# Sheet1.net
KiCad netlist of a schematic drawn in Altium Designer
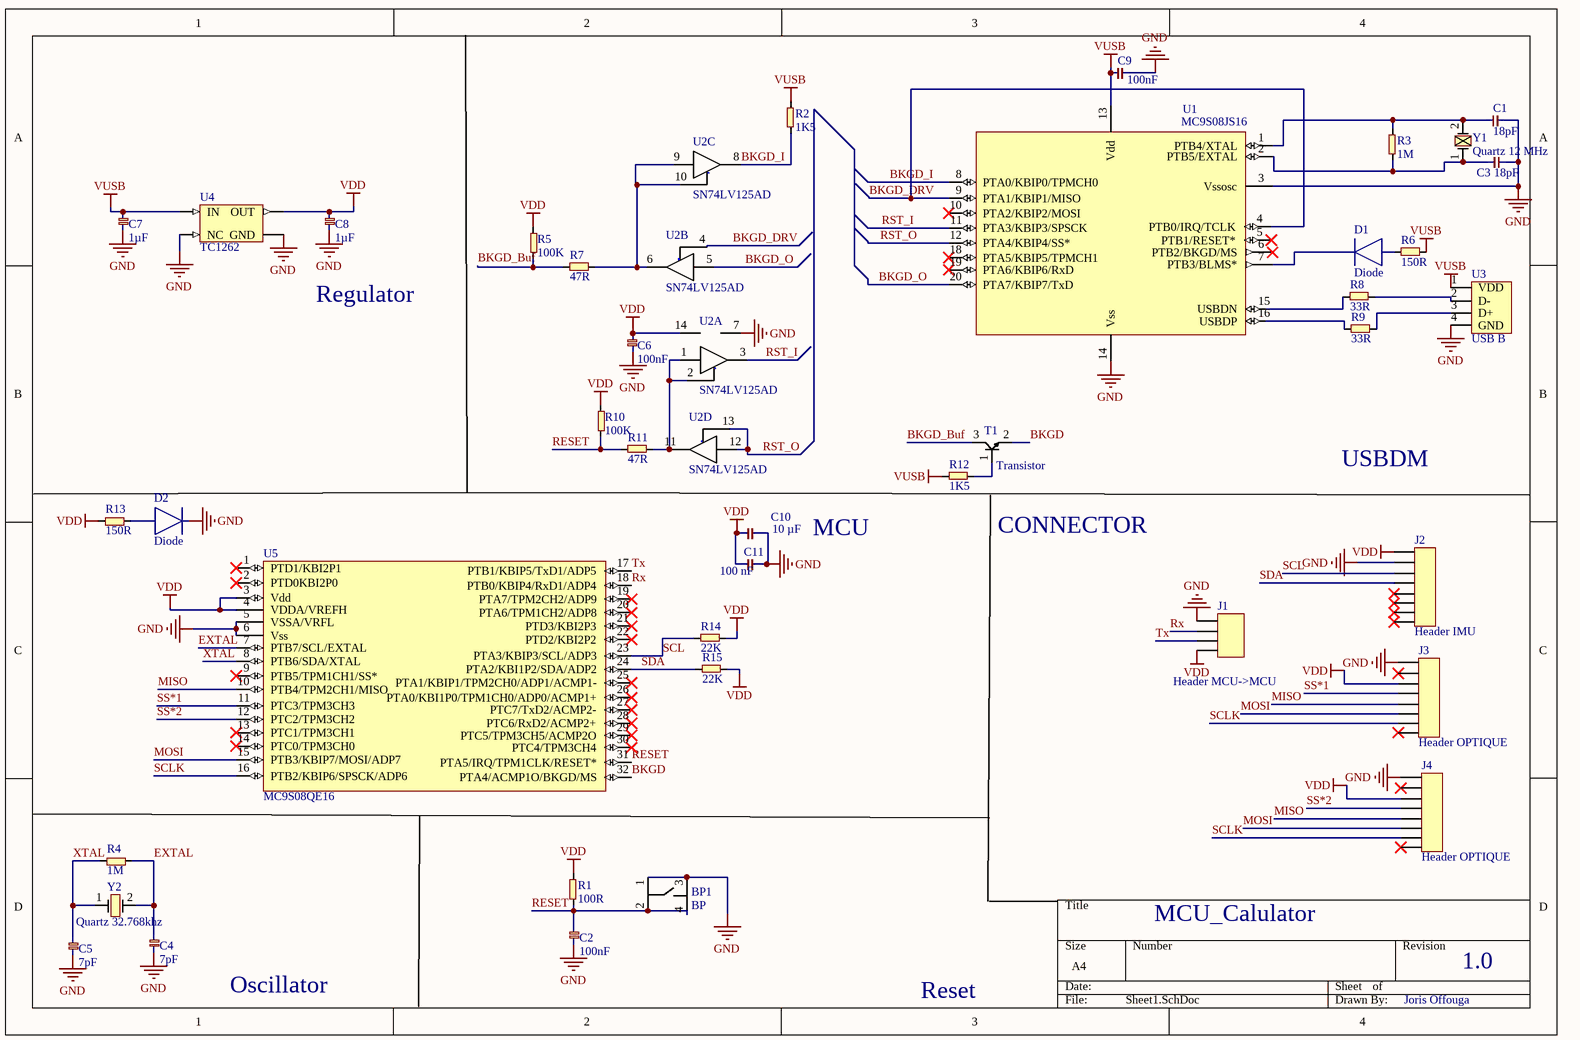
[diagram p0: Sheet1.SchDoc]

(export (version "E")
  (design (tool "Eeschema 10.0.6"))
  (components
    (comp (ref "BP1") (value "BP") (footprint "BP") (libsource (lib "Schlib1") (part "BP")))
    (comp (ref "C1")
      (value "18pF")
      (footprint "0805")
      (description "Condensateur")
      (libsource (lib "") (part "Condensateur_1"))
    )
    (comp (ref "C2")
      (value "100nF")
      (footprint "0805")
      (description "Condensateur")
      (libsource (lib "") (part "Condensateur_2"))
    )
    (comp (ref "C3")
      (value "18pF")
      (footprint "0805")
      (description "Condensateur")
      (libsource (lib "") (part "Condensateur_1"))
    )
    (comp (ref "C4")
      (value "7pF")
      (footprint "0805")
      (description "Condensateur")
      (libsource (lib "") (part "Condensateur_2"))
    )
    (comp (ref "C5")
      (value "7pF")
      (footprint "0805")
      (description "Condensateur")
      (libsource (lib "") (part "Condensateur_2"))
    )
    (comp (ref "C6")
      (value "100nF")
      (footprint "0805")
      (description "Condensateur")
      (libsource (lib "Schlib1") (part "Condensateur"))
    )
    (comp (ref "C7")
      (value "1µF")
      (footprint "0805")
      (description "Condensateur")
      (libsource (lib "") (part "Condensateur_2"))
    )
    (comp (ref "C8")
      (value "1µF")
      (footprint "0805")
      (description "Condensateur")
      (libsource (lib "") (part "Condensateur_2"))
    )
    (comp (ref "C9")
      (value "100nF")
      (footprint "0805")
      (description "Condensateur")
      (libsource (lib "") (part "Condensateur_1"))
    )
    (comp (ref "C10")
      (value "10 µF")
      (footprint "0805")
      (description "Condensateur")
      (libsource (lib "") (part "Condensateur_1"))
    )
    (comp (ref "C11")
      (value "100 nF")
      (footprint "0805")
      (description "Condensateur")
      (libsource (lib "") (part "Condensateur_1"))
    )
    (comp (ref "D1")
      (value "Diode")
      (footprint "led")
      (description "led")
      (libsource (lib "Schlib1") (part "Diode"))
    )
    (comp (ref "D2")
      (value "Diode")
      (footprint "led")
      (description "led")
      (libsource (lib "Schlib1") (part "Diode"))
    )
    (comp (ref "J1")
      (value "Header MCU->MCU")
      (footprint "Header 4")
      (libsource (lib "Schlib1") (part "Header 4"))
    )
    (comp (ref "J2") (value "Header IMU") (footprint "Header 8") (libsource (lib "Schlib1") (part "Header")))
    (comp (ref "J3")
      (value "Header OPTIQUE")
      (footprint "Header 8")
      (libsource (lib "Schlib1") (part "Header"))
    )
    (comp (ref "J4")
      (value "Header OPTIQUE")
      (footprint "Header 8")
      (libsource (lib "Schlib1") (part "Header"))
    )
    (comp (ref "R1") (value "100R") (footprint "0805") (libsource (lib "") (part "Resistance_2")))
    (comp (ref "R2") (value "1K5") (footprint "0805") (libsource (lib "") (part "Resistance_2")))
    (comp (ref "R3") (value "1M") (footprint "0805") (libsource (lib "") (part "Resistance_2")))
    (comp (ref "R4") (value "1M") (footprint "0805") (libsource (lib "") (part "Resistance_3")))
    (comp (ref "R5") (value "100K") (footprint "0805") (libsource (lib "Schlib1") (part "Resistance")))
    (comp (ref "R6") (value "150R") (footprint "0805") (libsource (lib "") (part "Resistance_1")))
    (comp (ref "R7") (value "47R") (footprint "0805") (libsource (lib "") (part "Resistance_1")))
    (comp (ref "R8") (value "33R") (footprint "0805") (libsource (lib "") (part "Resistance_1")))
    (comp (ref "R9") (value "33R") (footprint "0805") (libsource (lib "") (part "Resistance_1")))
    (comp (ref "R10") (value "100K") (footprint "0805") (libsource (lib "Schlib1") (part "Resistance")))
    (comp (ref "R11") (value "47R") (footprint "0805") (libsource (lib "") (part "Resistance_1")))
    (comp (ref "R12") (value "1K5") (footprint "0805") (libsource (lib "") (part "Resistance_1")))
    (comp (ref "R13") (value "150R") (footprint "0805") (libsource (lib "") (part "Resistance_3")))
    (comp (ref "R14") (value "22K") (footprint "0805") (libsource (lib "") (part "Resistance_1")))
    (comp (ref "R15") (value "22K") (footprint "0805") (libsource (lib "") (part "Resistance_1")))
    (comp (ref "T1")
      (value "Transistor")
      (footprint "Transistor")
      (libsource (lib "Schlib1") (part "Transistor"))
    )
    (comp (ref "U1")
      (value "MC9S08JS16")
      (footprint "MC9S08JS16")
      (libsource (lib "Schlib1") (part "MC9S08JS16"))
    )
    (comp (ref "U2")
      (value "SN74LV125AD")
      (footprint "SN74LV125AD")
      (libsource (lib "Schlib1") (part "SN74LV125AD"))
    )
    (comp (ref "U3") (value "USB B") (footprint "USB_B") (libsource (lib "Schlib1") (part "USB B")))
    (comp (ref "U4") (value "TC1262") (footprint "TC1262") (libsource (lib "Schlib1") (part "TC1262")))
    (comp (ref "U5")
      (value "MC9S08QE16")
      (footprint "LQFP_32")
      (libsource (lib "Schlib1") (part "MC9S08QE16"))
    )
    (comp (ref "Y1") (value "Quartz 12 MHz") (footprint "Quartz") (libsource (lib "Schlib1") (part "Quartz")))
    (comp (ref "Y2")
      (value "Quartz 32.768khz")
      (footprint "Quartz 32.768kHZ")
      (libsource (lib "Schlib1") (part "Quartz 32.768khz"))
    )
  )
  (nets
    (net (code "1") (name "/BKGD") (class "Default")
      (node (ref "T1") (pin "2") (pinfunction "2_2") (pintype "passive"))
      (node (ref "U5") (pin "32") (pinfunction "PTA4/ACMP1O/BKGD/MS_32") (pintype "bidirectional"))
    )
    (net (code "2") (name "/BKGD_Buf") (class "Default")
      (node (ref "R5") (pin "2") (pinfunction "2_2") (pintype "passive"))
      (node (ref "R7") (pin "1") (pinfunction "1_1") (pintype "passive"))
      (node (ref "T1") (pin "3") (pinfunction "3_3") (pintype "passive"))
    )
    (net (code "3") (name "/BKGD_DRV") (class "Default")
      (node (ref "U1") (pin "4") (pinfunction "PTB0/IRQ/TCLK_4") (pintype "bidirectional"))
      (node (ref "U1") (pin "9") (pinfunction "PTA1/KBIP1/MISO_9") (pintype "bidirectional"))
      (node (ref "U2") (pin "4") (pinfunction "4_4") (pintype "passive"))
    )
    (net (code "4") (name "/BKGD_I") (class "Default")
      (node (ref "R2") (pin "1") (pinfunction "1_1") (pintype "passive"))
      (node (ref "U1") (pin "8") (pinfunction "PTA0/KBIP0/TPMCH0_8") (pintype "bidirectional"))
      (node (ref "U2") (pin "8") (pinfunction "8_8") (pintype "passive"))
    )
    (net (code "5") (name "/BKGD_O") (class "Default")
      (node (ref "U1") (pin "20") (pinfunction "PTA7/KBIP7/TxD_20") (pintype "bidirectional"))
      (node (ref "U2") (pin "5") (pinfunction "5_5") (pintype "passive"))
    )
    (net (code "6") (name "/EXTAL") (class "Default")
      (node (ref "C4") (pin "2") (pinfunction "2_2") (pintype "passive"))
      (node (ref "R4") (pin "1") (pinfunction "1_1") (pintype "passive"))
      (node (ref "U5") (pin "7") (pinfunction "PTB7/SCL/EXTAL_7") (pintype "bidirectional"))
      (node (ref "Y2") (pin "2") (pinfunction "19_2") (pintype "passive"))
    )
    (net (code "7") (name "/MISO") (class "Default")
      (node (ref "J3") (pin "5") (pinfunction "5_5") (pintype "passive"))
      (node (ref "J4") (pin "5") (pinfunction "5_5") (pintype "passive"))
      (node (ref "U5") (pin "10") (pinfunction "PTB4/TPM2CH1/MISO_10") (pintype "bidirectional"))
    )
    (net (code "8") (name "/MOSI") (class "Default")
      (node (ref "J3") (pin "6") (pinfunction "6_6") (pintype "passive"))
      (node (ref "J4") (pin "6") (pinfunction "6_6") (pintype "passive"))
      (node (ref "U5") (pin "15") (pinfunction "PTB3/KBIP7/MOSI/ADP7_15") (pintype "bidirectional"))
    )
    (net (code "9") (name "/RESET") (class "Default")
      (node (ref "BP1") (pin "2") (pinfunction "2_2") (pintype "passive"))
      (node (ref "BP1") (pin "4") (pinfunction "4_4") (pintype "passive"))
      (node (ref "C2") (pin "2") (pinfunction "2_2") (pintype "passive"))
      (node (ref "R1") (pin "1") (pinfunction "1_1") (pintype "passive"))
      (node (ref "R10") (pin "2") (pinfunction "2_2") (pintype "passive"))
      (node (ref "R11") (pin "1") (pinfunction "1_1") (pintype "passive"))
      (node (ref "U5") (pin "31") (pinfunction "PTA5/IRQ/TPM1CLK/RESET*_31") (pintype "bidirectional"))
    )
    (net (code "10") (name "/RST_I") (class "Default")
      (node (ref "U1") (pin "11") (pinfunction "PTA3/KBIP3/SPSCK_11") (pintype "bidirectional"))
      (node (ref "U2") (pin "3") (pinfunction "3_3") (pintype "passive"))
    )
    (net (code "11") (name "/RST_O") (class "Default")
      (node (ref "U1") (pin "12") (pinfunction "PTA4/KBIP4/SS*_12") (pintype "bidirectional"))
      (node (ref "U2") (pin "12") (pinfunction "12_12") (pintype "passive"))
      (node (ref "U2") (pin "13") (pinfunction "13_13") (pintype "passive"))
    )
    (net (code "12") (name "/Rx") (class "Default")
      (node (ref "J1") (pin "2") (pinfunction "2_2") (pintype "passive"))
      (node (ref "U5") (pin "18") (pinfunction "PTB0/KBIP4/RxD1/ADP4_18") (pintype "bidirectional"))
    )
    (net (code "13") (name "/SCL") (class "Default")
      (node (ref "J2") (pin "3") (pinfunction "3_3") (pintype "passive"))
      (node (ref "R14") (pin "1") (pinfunction "1_1") (pintype "passive"))
      (node (ref "U5") (pin "23") (pinfunction "PTA3/KBIP3/SCL/ADP3_23") (pintype "bidirectional"))
    )
    (net (code "14") (name "/SCLK") (class "Default")
      (node (ref "J3") (pin "7") (pinfunction "7_7") (pintype "passive"))
      (node (ref "J4") (pin "7") (pinfunction "7_7") (pintype "passive"))
      (node (ref "U5") (pin "16") (pinfunction "PTB2/KBIP6/SPSCK/ADP6_16") (pintype "bidirectional"))
    )
    (net (code "15") (name "/SDA") (class "Default")
      (node (ref "J2") (pin "4") (pinfunction "4_4") (pintype "passive"))
      (node (ref "R15") (pin "1") (pinfunction "1_1") (pintype "passive"))
      (node (ref "U5") (pin "24") (pinfunction "PTA2/KBI1P2/SDA/ADP2_24") (pintype "bidirectional"))
    )
    (net (code "16") (name "/SS*1") (class "Default")
      (node (ref "J3") (pin "4") (pinfunction "4_4") (pintype "passive"))
      (node (ref "U5") (pin "11") (pinfunction "PTC3/TPM3CH3_11") (pintype "bidirectional"))
    )
    (net (code "17") (name "/SS*2") (class "Default")
      (node (ref "J4") (pin "4") (pinfunction "4_4") (pintype "passive"))
      (node (ref "U5") (pin "12") (pinfunction "PTC2/TPM3CH2_12") (pintype "bidirectional"))
    )
    (net (code "18") (name "/Tx") (class "Default")
      (node (ref "J1") (pin "3") (pinfunction "3_3") (pintype "passive"))
      (node (ref "U5") (pin "17") (pinfunction "PTB1/KBIP5/TxD1/ADP5_17") (pintype "bidirectional"))
    )
    (net (code "19") (name "/XTAL") (class "Default")
      (node (ref "C5") (pin "2") (pinfunction "2_2") (pintype "passive"))
      (node (ref "R4") (pin "2") (pinfunction "2_2") (pintype "passive"))
      (node (ref "U5") (pin "8") (pinfunction "PTB6/SDA/XTAL_8") (pintype "bidirectional"))
      (node (ref "Y2") (pin "1") (pinfunction "20_1") (pintype "passive"))
    )
    (net (code "20") (name "GND") (class "Default")
      (node (ref "BP1") (pin "1") (pinfunction "1_1") (pintype "passive"))
      (node (ref "BP1") (pin "3") (pinfunction "3_3") (pintype "passive"))
      (node (ref "C1") (pin "2") (pinfunction "2_2") (pintype "passive"))
      (node (ref "C10") (pin "2") (pinfunction "2_2") (pintype "passive"))
      (node (ref "C11") (pin "2") (pinfunction "2_2") (pintype "passive"))
      (node (ref "C2") (pin "1") (pinfunction "1_1") (pintype "passive"))
      (node (ref "C3") (pin "2") (pinfunction "2_2") (pintype "passive"))
      (node (ref "C4") (pin "1") (pinfunction "1_1") (pintype "passive"))
      (node (ref "C5") (pin "1") (pinfunction "1_1") (pintype "passive"))
      (node (ref "C6") (pin "2") (pinfunction "2_2") (pintype "passive"))
      (node (ref "C7") (pin "1") (pinfunction "1_1") (pintype "passive"))
      (node (ref "C8") (pin "1") (pinfunction "1_1") (pintype "passive"))
      (node (ref "C9") (pin "2") (pinfunction "2_2") (pintype "passive"))
      (node (ref "D2") (pin "2") (pinfunction "3_2") (pintype "passive"))
      (node (ref "J1") (pin "1") (pinfunction "1_1") (pintype "passive"))
      (node (ref "J2") (pin "2") (pinfunction "2_2") (pintype "passive"))
      (node (ref "J3") (pin "1") (pinfunction "1_1") (pintype "passive"))
      (node (ref "J4") (pin "1") (pinfunction "1_1") (pintype "passive"))
      (node (ref "U1") (pin "14") (pinfunction "Vss_14") (pintype "passive"))
      (node (ref "U1") (pin "3") (pinfunction "Vssosc_3") (pintype "passive"))
      (node (ref "U2") (pin "7") (pinfunction "7_7") (pintype "passive"))
      (node (ref "U3") (pin "4") (pinfunction "GND_4") (pintype "passive"))
      (node (ref "U4") (pin "2") (pinfunction "GND_2") (pintype "passive"))
      (node (ref "U4") (pin "4") (pinfunction "NC_4") (pintype "input"))
      (node (ref "U5") (pin "5") (pinfunction "VSSA/VRFL_5") (pintype "passive"))
      (node (ref "U5") (pin "6") (pinfunction "Vss_6") (pintype "passive"))
    )
    (net (code "21") (name "Net-(D1-3-Pad1)") (class "Default")
      (node (ref "D1") (pin "1") (pinfunction "3_1") (pintype "passive"))
      (node (ref "R6") (pin "1") (pinfunction "1_1") (pintype "passive"))
    )
    (net (code "22") (name "Net-(D2-3-Pad1)") (class "Default")
      (node (ref "D2") (pin "1") (pinfunction "3_1") (pintype "passive"))
      (node (ref "R13") (pin "1") (pinfunction "1_1") (pintype "passive"))
    )
    (net (code "23") (name "Net-(R7-Pad2)") (class "Default")
      (node (ref "R7") (pin "2") (pinfunction "2_2") (pintype "passive"))
      (node (ref "U2") (pin "10") (pinfunction "10_10") (pintype "passive"))
      (node (ref "U2") (pin "6") (pinfunction "6_6") (pintype "passive"))
      (node (ref "U2") (pin "9") (pinfunction "9_9") (pintype "passive"))
    )
    (net (code "24") (name "Net-(R11-Pad2)") (class "Default")
      (node (ref "R11") (pin "2") (pinfunction "2_2") (pintype "passive"))
      (node (ref "U2") (pin "1") (pinfunction "1_1") (pintype "passive"))
      (node (ref "U2") (pin "11") (pinfunction "11_11") (pintype "passive"))
      (node (ref "U2") (pin "2") (pinfunction "2_2") (pintype "passive"))
    )
    (net (code "25") (name "Net-(R12-Pad2)") (class "Default")
      (node (ref "R12") (pin "2") (pinfunction "2_2") (pintype "passive"))
      (node (ref "T1") (pin "1") (pinfunction "1_1") (pintype "passive"))
    )
    (net (code "26") (name "Net-(U1-PTB3{slash}BLMS*)") (class "Default")
      (node (ref "D1") (pin "2") (pinfunction "3_2") (pintype "passive"))
      (node (ref "U1") (pin "7") (pinfunction "PTB3/BLMS*_7") (pintype "output"))
    )
    (net (code "27") (name "Net-(U1-PTB4{slash}XTAL)") (class "Default")
      (node (ref "C1") (pin "1") (pinfunction "1_1") (pintype "passive"))
      (node (ref "R3") (pin "2") (pinfunction "2_2") (pintype "passive"))
      (node (ref "U1") (pin "1") (pinfunction "PTB4/XTAL_1") (pintype "bidirectional"))
      (node (ref "Y1") (pin "2") (pinfunction "2_2") (pintype "passive"))
    )
    (net (code "28") (name "Net-(U1-PTB5{slash}EXTAL)") (class "Default")
      (node (ref "C3") (pin "1") (pinfunction "1_1") (pintype "passive"))
      (node (ref "R3") (pin "1") (pinfunction "1_1") (pintype "passive"))
      (node (ref "U1") (pin "2") (pinfunction "PTB5/EXTAL_2") (pintype "bidirectional"))
      (node (ref "Y1") (pin "1") (pinfunction "1_1") (pintype "passive"))
    )
    (net (code "29") (name "Net-(U1-USBDN)") (class "Default")
      (node (ref "R8") (pin "1") (pinfunction "1_1") (pintype "passive"))
      (node (ref "U1") (pin "15") (pinfunction "USBDN_15") (pintype "bidirectional"))
    )
    (net (code "30") (name "Net-(U1-USBDP)") (class "Default")
      (node (ref "R9") (pin "1") (pinfunction "1_1") (pintype "passive"))
      (node (ref "U1") (pin "16") (pinfunction "USBDP_16") (pintype "bidirectional"))
    )
    (net (code "31") (name "Net-(U3-D+)") (class "Default")
      (node (ref "R9") (pin "2") (pinfunction "2_2") (pintype "passive"))
      (node (ref "U3") (pin "3") (pinfunction "D+_3") (pintype "passive"))
    )
    (net (code "32") (name "Net-(U3-D-)") (class "Default")
      (node (ref "R8") (pin "2") (pinfunction "2_2") (pintype "passive"))
      (node (ref "U3") (pin "2") (pinfunction "D-_2") (pintype "passive"))
    )
    (net (code "33") (name "VDD") (class "Default")
      (node (ref "C10") (pin "1") (pinfunction "1_1") (pintype "passive"))
      (node (ref "C11") (pin "1") (pinfunction "1_1") (pintype "passive"))
      (node (ref "C6") (pin "1") (pinfunction "1_1") (pintype "passive"))
      (node (ref "C8") (pin "2") (pinfunction "2_2") (pintype "passive"))
      (node (ref "J1") (pin "4") (pinfunction "4_4") (pintype "passive"))
      (node (ref "J2") (pin "1") (pinfunction "1_1") (pintype "passive"))
      (node (ref "J3") (pin "3") (pinfunction "3_3") (pintype "passive"))
      (node (ref "J4") (pin "3") (pinfunction "3_3") (pintype "passive"))
      (node (ref "R1") (pin "2") (pinfunction "2_2") (pintype "passive"))
      (node (ref "R10") (pin "1") (pinfunction "1_1") (pintype "passive"))
      (node (ref "R13") (pin "2") (pinfunction "2_2") (pintype "passive"))
      (node (ref "R14") (pin "2") (pinfunction "2_2") (pintype "passive"))
      (node (ref "R15") (pin "2") (pinfunction "2_2") (pintype "passive"))
      (node (ref "R5") (pin "1") (pinfunction "1_1") (pintype "passive"))
      (node (ref "U2") (pin "14") (pinfunction "14_14") (pintype "passive"))
      (node (ref "U4") (pin "3") (pinfunction "OUT_3") (pintype "output"))
      (node (ref "U5") (pin "3") (pinfunction "Vdd_3") (pintype "bidirectional"))
      (node (ref "U5") (pin "4") (pinfunction "VDDA/VREFH_4") (pintype "passive"))
    )
    (net (code "34") (name "VUSB") (class "Default")
      (node (ref "C7") (pin "2") (pinfunction "2_2") (pintype "passive"))
      (node (ref "C9") (pin "1") (pinfunction "1_1") (pintype "passive"))
      (node (ref "R12") (pin "1") (pinfunction "1_1") (pintype "passive"))
      (node (ref "R2") (pin "2") (pinfunction "2_2") (pintype "passive"))
      (node (ref "R6") (pin "2") (pinfunction "2_2") (pintype "passive"))
      (node (ref "U1") (pin "13") (pinfunction "Vdd_13") (pintype "passive"))
      (node (ref "U3") (pin "1") (pinfunction "VDD_1") (pintype "passive"))
      (node (ref "U4") (pin "1") (pinfunction "IN_1") (pintype "input"))
    )
    (net (code "35") (name "unconnected-(J2-Pad5)") (class "Default")
      (node (ref "J2") (pin "5") (pinfunction "5_5") (pintype "passive+no_connect"))
    )
    (net (code "36") (name "unconnected-(J2-Pad6)") (class "Default")
      (node (ref "J2") (pin "6") (pinfunction "6_6") (pintype "passive+no_connect"))
    )
    (net (code "37") (name "unconnected-(J2-Pad7)") (class "Default")
      (node (ref "J2") (pin "7") (pinfunction "7_7") (pintype "passive+no_connect"))
    )
    (net (code "38") (name "unconnected-(J2-Pad8)") (class "Default")
      (node (ref "J2") (pin "8") (pinfunction "8_8") (pintype "passive+no_connect"))
    )
    (net (code "39") (name "unconnected-(J3-Pad2)") (class "Default")
      (node (ref "J3") (pin "2") (pinfunction "2_2") (pintype "passive+no_connect"))
    )
    (net (code "40") (name "unconnected-(J3-Pad8)") (class "Default")
      (node (ref "J3") (pin "8") (pinfunction "8_8") (pintype "passive+no_connect"))
    )
    (net (code "41") (name "unconnected-(J4-Pad2)") (class "Default")
      (node (ref "J4") (pin "2") (pinfunction "2_2") (pintype "passive+no_connect"))
    )
    (net (code "42") (name "unconnected-(J4-Pad8)") (class "Default")
      (node (ref "J4") (pin "8") (pinfunction "8_8") (pintype "passive+no_connect"))
    )
    (net (code "43") (name "unconnected-(U1-PTA2{slash}KBIP2{slash}MOSI-Pad10)") (class "Default")
      (node (ref "U1") (pin "10") (pinfunction "PTA2/KBIP2/MOSI_10") (pintype "bidirectional+no_connect"))
    )
    (net (code "44") (name "unconnected-(U1-PTA5{slash}KBIP5{slash}TPMCH1-Pad18)") (class "Default")
      (node (ref "U1") (pin "18") (pinfunction "PTA5/KBIP5/TPMCH1_18") (pintype "bidirectional+no_connect"))
    )
    (net (code "45") (name "unconnected-(U1-PTA6{slash}KBIP6{slash}RxD-Pad19)") (class "Default")
      (node (ref "U1") (pin "19") (pinfunction "PTA6/KBIP6/RxD_19") (pintype "bidirectional+no_connect"))
    )
    (net (code "46") (name "unconnected-(U1-PTB1{slash}RESET*-Pad5)") (class "Default")
      (node (ref "U1") (pin "5") (pinfunction "PTB1/RESET*_5") (pintype "bidirectional+no_connect"))
    )
    (net (code "47") (name "unconnected-(U1-PTB2{slash}BKGD{slash}MS-Pad6)") (class "Default")
      (node (ref "U1") (pin "6") (pinfunction "PTB2/BKGD/MS_6") (pintype "output+no_connect"))
    )
    (net (code "48") (name "unconnected-(U5-PTA0{slash}KBI1P0{slash}TPM1CH0{slash}ADP0{slash}ACMP1+-Pad26)") (class "Default")
      (node (ref "U5") (pin "26") (pinfunction "PTA0/KBI1P0/TPM1CH0/ADP0/ACMP1+_26") (pintype "bidirectional+no_connect"))
    )
    (net (code "49") (name "unconnected-(U5-PTA1{slash}KBIP1{slash}TPM2CH0{slash}ADP1{slash}ACMP1--Pad25)") (class "Default")
      (node (ref "U5") (pin "25") (pinfunction "PTA1/KBIP1/TPM2CH0/ADP1/ACMP1-_25") (pintype "bidirectional+no_connect"))
    )
    (net (code "50") (name "unconnected-(U5-PTA6{slash}TPM1CH2{slash}ADP8-Pad20)") (class "Default")
      (node (ref "U5") (pin "20") (pinfunction "PTA6/TPM1CH2/ADP8_20") (pintype "bidirectional+no_connect"))
    )
    (net (code "51") (name "unconnected-(U5-PTA7{slash}TPM2CH2{slash}ADP9-Pad19)") (class "Default")
      (node (ref "U5") (pin "19") (pinfunction "PTA7/TPM2CH2/ADP9_19") (pintype "bidirectional+no_connect"))
    )
    (net (code "52") (name "unconnected-(U5-PTB5{slash}TPM1CH1{slash}SS*-Pad9)") (class "Default")
      (node (ref "U5") (pin "9") (pinfunction "PTB5/TPM1CH1/SS*_9") (pintype "bidirectional+no_connect"))
    )
    (net (code "53") (name "unconnected-(U5-PTC0{slash}TPM3CH0-Pad14)") (class "Default")
      (node (ref "U5") (pin "14") (pinfunction "PTC0/TPM3CH0_14") (pintype "bidirectional+no_connect"))
    )
    (net (code "54") (name "unconnected-(U5-PTC1{slash}TPM3CH1-Pad13)") (class "Default")
      (node (ref "U5") (pin "13") (pinfunction "PTC1/TPM3CH1_13") (pintype "bidirectional+no_connect"))
    )
    (net (code "55") (name "unconnected-(U5-PTC4{slash}TPM3CH4-Pad30)") (class "Default")
      (node (ref "U5") (pin "30") (pinfunction "PTC4/TPM3CH4_30") (pintype "bidirectional+no_connect"))
    )
    (net (code "56") (name "unconnected-(U5-PTC5{slash}TPM3CH5{slash}ACMP2O-Pad29)") (class "Default")
      (node (ref "U5") (pin "29") (pinfunction "PTC5/TPM3CH5/ACMP2O_29") (pintype "bidirectional+no_connect"))
    )
    (net (code "57") (name "unconnected-(U5-PTC6{slash}RxD2{slash}ACMP2+-Pad28)") (class "Default")
      (node (ref "U5") (pin "28") (pinfunction "PTC6/RxD2/ACMP2+_28") (pintype "bidirectional+no_connect"))
    )
    (net (code "58") (name "unconnected-(U5-PTC7{slash}TxD2{slash}ACMP2--Pad27)") (class "Default")
      (node (ref "U5") (pin "27") (pinfunction "PTC7/TxD2/ACMP2-_27") (pintype "bidirectional+no_connect"))
    )
    (net (code "59") (name "unconnected-(U5-PTD0KBI2P0-Pad2)") (class "Default")
      (node (ref "U5") (pin "2") (pinfunction "PTD0KBI2P0_2") (pintype "bidirectional+no_connect"))
    )
    (net (code "60") (name "unconnected-(U5-PTD1{slash}KBI2P1-Pad1)") (class "Default")
      (node (ref "U5") (pin "1") (pinfunction "PTD1/KBI2P1_1") (pintype "bidirectional+no_connect"))
    )
    (net (code "61") (name "unconnected-(U5-PTD2{slash}KBI2P2-Pad22)") (class "Default")
      (node (ref "U5") (pin "22") (pinfunction "PTD2/KBI2P2_22") (pintype "bidirectional+no_connect"))
    )
    (net (code "62") (name "unconnected-(U5-PTD3{slash}KBI2P3-Pad21)") (class "Default")
      (node (ref "U5") (pin "21") (pinfunction "PTD3/KBI2P3_21") (pintype "bidirectional+no_connect"))
    )
  )
)
